# Vaccum_Pump_Driver.net
KiCad netlist of a schematic drawn in Altium Designer
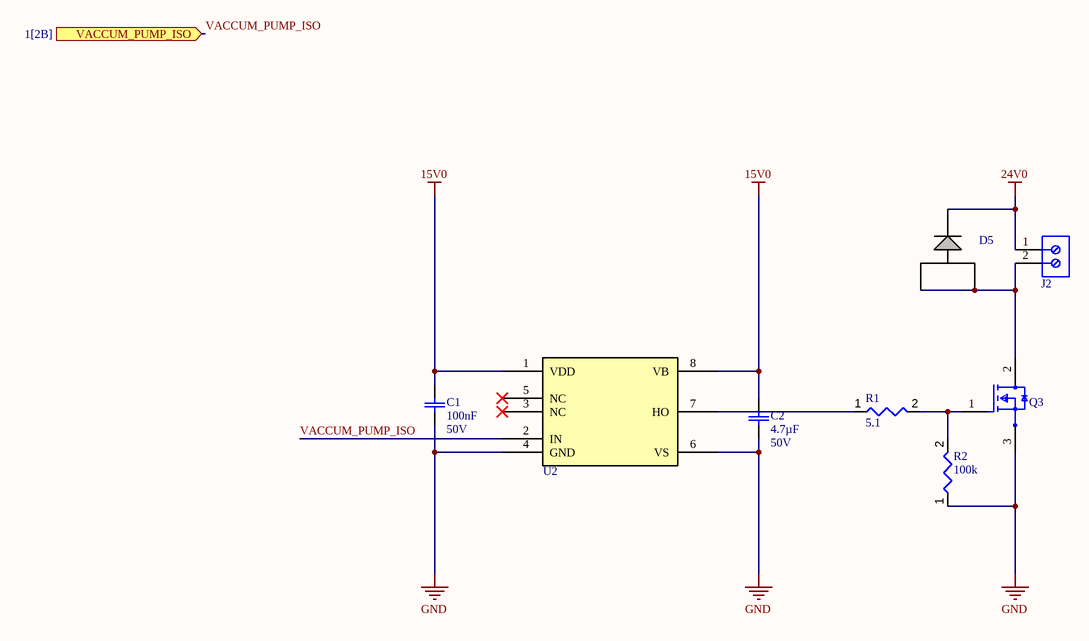
[diagram p0: Vaccum_Pump_Driver.SchDoc]

(export (version "E")
  (design (tool "Eeschema 10.0.6"))
  (components
    (comp (ref "C1")
      (value "100nF")
      (footprint "Generic Ceramic 0603 CAP")
      (fields
        (field (name "VOLTAGE RATING") "50V")
        (field (name "Comment") "CAP-MLCC_SMD-0603_MR-GCM_u_0.1uF_50V_10%_X8L")
      )
      (libsource (lib "Paulo Peixoto") (part "CAP_Ceramic"))
    )
    (comp (ref "C2")
      (value "4.7µF")
      (footprint "Generic Ceramic 0805 CAP")
      (fields
        (field (name "VOLTAGE RATING") "50V")
        (field (name "TOLERANCE") "10%")
        (field (name "Comment") "CAP-MLCC_SMD-0805_TDK-CGA_u_4.7uF_V_10%_X8R")
      )
      (libsource (lib "Paulo Peixoto") (part "CAP_Ceramic"))
    )
    (comp (ref "D5")
      (value "STPS1045B")
      (footprint "STPS1045B-Footprint-1")
      (description "Rectifier Diode, Schottky, 1 Phase, 1 Element, 10A, 45V V(RRM), Silicon, TO-252AA")
      (libsource (lib "Paulo Peixoto") (part "STPS1045B-Symbol-1"))
    )
    (comp (ref "J2")
      (value "691137710002")
      (footprint "691137710002")
      (description "2P Block Terminal")
      (libsource (lib "Paulo Peixoto") (part "Generic_2P_Block_Terminal"))
    )
    (comp (ref "Q3")
      (value "STD7NM50N")
      (footprint "STD7NM50N-Footprint-1")
      (description "N-channel 500V - 0.70 Ohm - 5A - TO-220 - TO-220FP - Ipak - Dpak")
      (libsource (lib "Paulo Peixoto") (part "Generic_N_FET"))
    )
    (comp (ref "R1")
      (value "5.1")
      (footprint "Generic_0805_RES")
      (fields
        (field (name "TOLERANCE") "1%")
        (field (name "POWER") "125mW")
        (field (name "Comment") "RES-TK_SMD-0805_VIS-CRCW_R_5.1R_1/10W_1%")
      )
      (libsource (lib "Paulo Peixoto") (part "Res"))
    )
    (comp (ref "R2")
      (value "100k")
      (footprint "Generic_0805_RES")
      (fields
        (field (name "POWER") "125mW")
        (field (name "TOLERANCE") "1%")
        (field (name "Comment") "RES-TK_SMD-0805_VIS-CRCW_K_100K_1/8W_1%")
      )
      (libsource (lib "Paulo Peixoto") (part "Res"))
    )
    (comp (ref "U2")
      (value "fan73711")
      (footprint "fan73711-Footprint-1")
      (description "Tape & Reel (TR) FAN73711 High-Side 2009 gate driver 25ns 125C 4A 4A 625mW")
      (libsource (lib "Paulo Peixoto") (part "fan73711-Symbol-1"))
    )
  )
  (nets
    (net (code "1") (name "/VACCUM_PUMP_ISO") (class "Default")
      (node (ref "U2") (pin "2") (pinfunction "IN_2") (pintype "passive"))
    )
    (net (code "2") (name "15V0") (class "Default")
      (node (ref "C1") (pin "2") (pinfunction "2_2") (pintype "passive"))
      (node (ref "C2") (pin "2") (pinfunction "2_2") (pintype "passive"))
      (node (ref "U2") (pin "1") (pinfunction "VDD_1") (pintype "power_in"))
      (node (ref "U2") (pin "8") (pinfunction "VB_8") (pintype "passive"))
    )
    (net (code "3") (name "24V0") (class "Default")
      (node (ref "D5") (pin "3") (pinfunction "2_3") (pintype "passive"))
      (node (ref "J2") (pin "1") (pinfunction "1_1") (pintype "passive"))
    )
    (net (code "4") (name "GND") (class "Default")
      (node (ref "C1") (pin "1") (pinfunction "1_1") (pintype "passive"))
      (node (ref "C2") (pin "1") (pinfunction "1_1") (pintype "passive"))
      (node (ref "Q3") (pin "3") (pinfunction "3_3") (pintype "passive"))
      (node (ref "R2") (pin "1") (pinfunction "1_1") (pintype "passive"))
      (node (ref "U2") (pin "4") (pinfunction "GND_4") (pintype "power_in"))
      (node (ref "U2") (pin "6") (pinfunction "VS_6") (pintype "passive"))
    )
    (net (code "5") (name "Net-(D5-3)") (class "Default")
      (node (ref "D5") (pin "1") (pinfunction "1_1") (pintype "passive"))
      (node (ref "D5") (pin "2") (pinfunction "3_2") (pintype "passive"))
      (node (ref "J2") (pin "2") (pinfunction "2_2") (pintype "passive"))
      (node (ref "Q3") (pin "2") (pinfunction "2_2") (pintype "passive"))
    )
    (net (code "6") (name "Net-(Q3-Pad1)") (class "Default")
      (node (ref "Q3") (pin "1") (pinfunction "1_1") (pintype "passive"))
      (node (ref "R1") (pin "2") (pinfunction "2_2") (pintype "passive"))
      (node (ref "R2") (pin "2") (pinfunction "2_2") (pintype "passive"))
    )
    (net (code "7") (name "Net-(U2-HO)") (class "Default")
      (node (ref "R1") (pin "1") (pinfunction "1_1") (pintype "passive"))
      (node (ref "U2") (pin "7") (pinfunction "HO_7") (pintype "passive"))
    )
    (net (code "8") (name "unconnected-(U2-NC-Pad3)") (class "Default")
      (node (ref "U2") (pin "3") (pinfunction "NC_3") (pintype "passive+no_connect"))
    )
    (net (code "9") (name "unconnected-(U2-NC-Pad5)") (class "Default")
      (node (ref "U2") (pin "5") (pinfunction "NC_5") (pintype "passive+no_connect"))
    )
  )
)
